# Schematic_car_like_pcb.net
KiCad netlist of a schematic drawn in Altium Designer
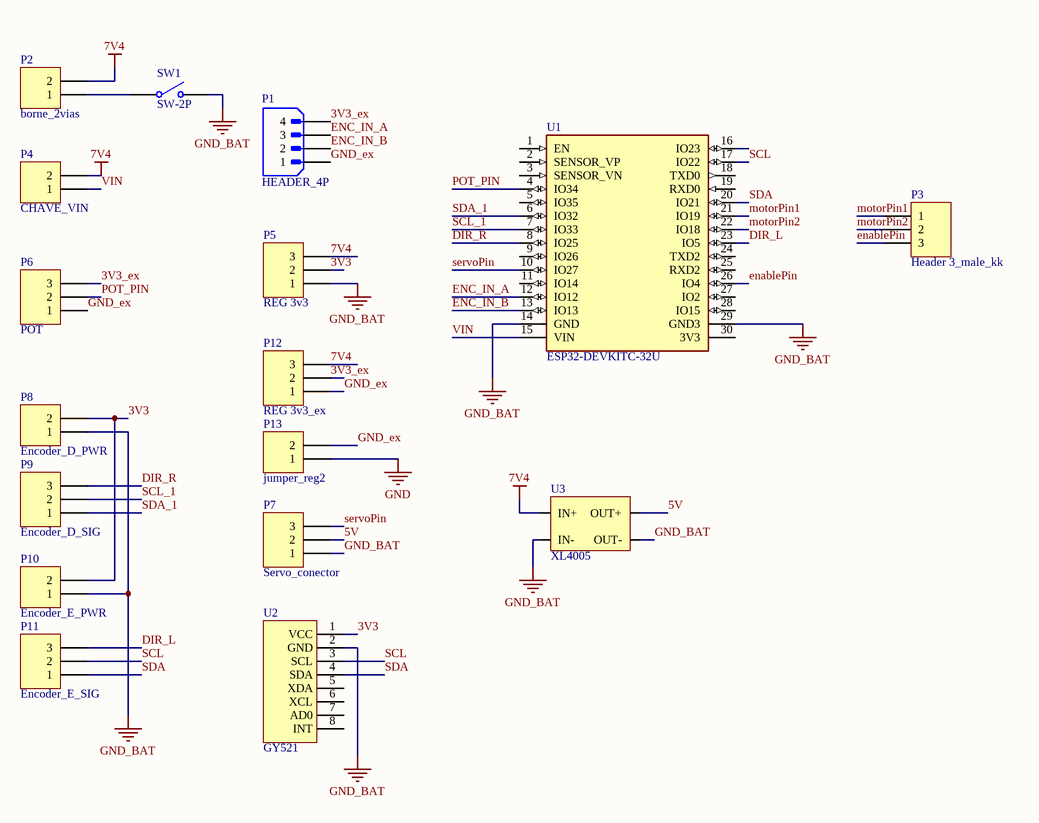
[diagram p0: Schematic_car_like_pcb.SchDoc]

(export (version "E")
  (design (tool "Eeschema 10.0.6"))
  (components
    (comp (ref "P1")
      (value "HEADER_4P")
      (footprint "HEADER_4PIN")
      (libsource (lib "CONNECTORS") (part "HEADER_4P"))
    )
    (comp (ref "P2")
      (value "borne_2vias")
      (footprint "BORNE_2VIAS")
      (libsource (lib "Connectors Library") (part "borne_2vias"))
    )
    (comp (ref "P3")
      (value "Header 3_male_kk")
      (footprint "HDR1X3_M - KK")
      (description "Header, 3-Pin")
      (fields (field (name "PUBLISHER") "Altium Limited"))
      (libsource (lib "") (part "Header 3_male_kk_1"))
    )
    (comp (ref "P4")
      (value "CHAVE_VIN")
      (footprint "HDR1X2_M - KK")
      (description "Header, 2-Pin")
      (fields (field (name "PUBLISHER") "Altium Limited"))
      (libsource (lib "Connectors Library") (part "Header 2_male_kk"))
    )
    (comp (ref "P5")
      (value "REG 3v3")
      (footprint "HDR1X3_F")
      (description "Header, 3-Pin")
      (fields (field (name "PUBLISHER") "Altium Limited"))
      (libsource (lib "Connectors Library") (part "Header 3_female"))
    )
    (comp (ref "P6")
      (value "POT")
      (footprint "HDR1X3_M - KK")
      (description "Header, 3-Pin")
      (fields (field (name "PUBLISHER") "Altium Limited"))
      (libsource (lib "Connectors Library") (part "Header 3_male_kk"))
    )
    (comp (ref "P7")
      (value "Servo_conector")
      (footprint "HDR1X3_M - KK")
      (description "Header, 3-Pin")
      (fields (field (name "PUBLISHER") "Altium Limited"))
      (libsource (lib "Connectors Library") (part "Header 3_male_kk"))
    )
    (comp (ref "P8")
      (value "Encoder_D_PWR")
      (footprint "HDR1X2_M - KK")
      (description "Header, 2-Pin")
      (fields (field (name "PUBLISHER") "Altium Limited"))
      (libsource (lib "Connectors Library") (part "Header 2_male_kk"))
    )
    (comp (ref "P9")
      (value "Encoder_D_SIG")
      (footprint "HDR1X3_M - KK")
      (description "Header, 3-Pin")
      (fields (field (name "PUBLISHER") "Altium Limited"))
      (libsource (lib "Connectors Library") (part "Header 3_male_kk"))
    )
    (comp (ref "P10")
      (value "Encoder_E_PWR")
      (footprint "HDR1X2_M - KK")
      (description "Header, 2-Pin")
      (fields (field (name "PUBLISHER") "Altium Limited"))
      (libsource (lib "Connectors Library") (part "Header 2_male_kk"))
    )
    (comp (ref "P11")
      (value "Encoder_E_SIG")
      (footprint "HDR1X3_M - KK")
      (description "Header, 3-Pin")
      (fields (field (name "PUBLISHER") "Altium Limited"))
      (libsource (lib "Connectors Library") (part "Header 3_male_kk"))
    )
    (comp (ref "P12")
      (value "REG 3v3_ex")
      (footprint "HDR1X3_F")
      (description "Header, 3-Pin")
      (fields (field (name "PUBLISHER") "Altium Limited"))
      (libsource (lib "Connectors Library") (part "Header 3_female"))
    )
    (comp (ref "P13")
      (value "jumper_reg2")
      (footprint "HDR1X2_M - KK")
      (description "Header, 2-Pin")
      (fields (field (name "PUBLISHER") "Altium Limited"))
      (libsource (lib "Connectors Library") (part "Header 2_male_kk"))
    )
    (comp (ref "SW1") (value "SW-2P") (footprint "SW-2") (libsource (lib "Devices") (part "SW-2P")))
    (comp (ref "U1")
      (value "ESP32-DEVKITC-32U")
      (footprint "ESP32S")
      (fields (field (name "MF") "Espressif Systems"))
      (libsource (lib "ESP32S") (part "ESP32-DEVKITC-32U"))
    )
    (comp (ref "U2") (value "GY521") (footprint "GY521") (libsource (lib "Devices") (part "GY521")))
    (comp (ref "U3") (value "XL4005") (footprint "XL4005") (libsource (lib "Devices") (part "XL4005")))
  )
  (nets
    (net (code "1") (name "/3V3") (class "Default")
      (node (ref "P10") (pin "2") (pinfunction "2_2") (pintype "passive"))
      (node (ref "P5") (pin "2") (pinfunction "2_2") (pintype "passive"))
      (node (ref "P8") (pin "2") (pinfunction "2_2") (pintype "passive"))
      (node (ref "U2") (pin "1") (pinfunction "VCC_1") (pintype "passive"))
    )
    (net (code "2") (name "/3V3_ex") (class "Default")
      (node (ref "P1") (pin "4") (pinfunction "4_4") (pintype "passive"))
      (node (ref "P12") (pin "2") (pinfunction "2_2") (pintype "passive"))
      (node (ref "P6") (pin "3") (pinfunction "3_3") (pintype "passive"))
    )
    (net (code "3") (name "/5V") (class "Default")
      (node (ref "P7") (pin "2") (pinfunction "2_2") (pintype "passive"))
      (node (ref "U3") (pin "4") (pinfunction "OUT+_4") (pintype "passive"))
    )
    (net (code "4") (name "/DIR_L") (class "Default")
      (node (ref "P11") (pin "3") (pinfunction "3_3") (pintype "passive"))
      (node (ref "U1") (pin "23") (pinfunction "IO5_23") (pintype "bidirectional"))
    )
    (net (code "5") (name "/DIR_R") (class "Default")
      (node (ref "P9") (pin "3") (pinfunction "3_3") (pintype "passive"))
      (node (ref "U1") (pin "8") (pinfunction "IO25_8") (pintype "bidirectional"))
    )
    (net (code "6") (name "/ENC_IN_A") (class "Default")
      (node (ref "P1") (pin "3") (pinfunction "3_3") (pintype "passive"))
      (node (ref "U1") (pin "12") (pinfunction "IO12_12") (pintype "bidirectional"))
    )
    (net (code "7") (name "/ENC_IN_B") (class "Default")
      (node (ref "P1") (pin "2") (pinfunction "2_2") (pintype "passive"))
      (node (ref "U1") (pin "13") (pinfunction "IO13_13") (pintype "bidirectional"))
    )
    (net (code "8") (name "/GND_ex") (class "Default")
      (node (ref "P1") (pin "1") (pinfunction "1_1") (pintype "passive"))
      (node (ref "P12") (pin "1") (pinfunction "1_1") (pintype "passive"))
      (node (ref "P13") (pin "2") (pinfunction "2_2") (pintype "passive"))
      (node (ref "P6") (pin "1") (pinfunction "1_1") (pintype "passive"))
    )
    (net (code "9") (name "/POT_PIN") (class "Default")
      (node (ref "P6") (pin "2") (pinfunction "2_2") (pintype "passive"))
      (node (ref "U1") (pin "4") (pinfunction "IO34_4") (pintype "bidirectional"))
    )
    (net (code "10") (name "/SCL") (class "Default")
      (node (ref "P11") (pin "2") (pinfunction "2_2") (pintype "passive"))
      (node (ref "U1") (pin "17") (pinfunction "IO22_17") (pintype "bidirectional"))
      (node (ref "U2") (pin "3") (pinfunction "SCL_3") (pintype "passive"))
    )
    (net (code "11") (name "/SCL_1") (class "Default")
      (node (ref "P9") (pin "2") (pinfunction "2_2") (pintype "passive"))
      (node (ref "U1") (pin "7") (pinfunction "IO33_7") (pintype "bidirectional"))
    )
    (net (code "12") (name "/SDA") (class "Default")
      (node (ref "P11") (pin "1") (pinfunction "1_1") (pintype "passive"))
      (node (ref "U1") (pin "20") (pinfunction "IO21_20") (pintype "bidirectional"))
      (node (ref "U2") (pin "4") (pinfunction "SDA_4") (pintype "passive"))
    )
    (net (code "13") (name "/SDA_1") (class "Default")
      (node (ref "P9") (pin "1") (pinfunction "1_1") (pintype "passive"))
      (node (ref "U1") (pin "6") (pinfunction "IO32_6") (pintype "bidirectional"))
    )
    (net (code "14") (name "/VIN") (class "Default")
      (node (ref "P4") (pin "1") (pinfunction "1_1") (pintype "passive"))
      (node (ref "U1") (pin "15") (pinfunction "VIN_15") (pintype "power_in"))
    )
    (net (code "15") (name "/enablePin") (class "Default")
      (node (ref "P3") (pin "3") (pinfunction "3_3") (pintype "passive"))
      (node (ref "U1") (pin "26") (pinfunction "IO4_26") (pintype "bidirectional"))
    )
    (net (code "16") (name "/motorPin1") (class "Default")
      (node (ref "P3") (pin "1") (pinfunction "1_1") (pintype "passive"))
      (node (ref "U1") (pin "21") (pinfunction "IO19_21") (pintype "bidirectional"))
    )
    (net (code "17") (name "/motorPin2") (class "Default")
      (node (ref "P3") (pin "2") (pinfunction "2_2") (pintype "passive"))
      (node (ref "U1") (pin "22") (pinfunction "IO18_22") (pintype "bidirectional"))
    )
    (net (code "18") (name "/servoPin") (class "Default")
      (node (ref "P7") (pin "3") (pinfunction "3_3") (pintype "passive"))
      (node (ref "U1") (pin "10") (pinfunction "IO27_10") (pintype "bidirectional"))
    )
    (net (code "19") (name "7V4") (class "Default")
      (node (ref "P12") (pin "3") (pinfunction "3_3") (pintype "passive"))
      (node (ref "P2") (pin "2") (pinfunction "2_2") (pintype "passive"))
      (node (ref "P4") (pin "2") (pinfunction "2_2") (pintype "passive"))
      (node (ref "P5") (pin "3") (pinfunction "3_3") (pintype "passive"))
      (node (ref "U3") (pin "2") (pinfunction "IN+_2") (pintype "passive"))
    )
    (net (code "20") (name "GND") (class "Default")
      (node (ref "P13") (pin "1") (pinfunction "1_1") (pintype "passive"))
    )
    (net (code "21") (name "GND_BAT") (class "Default")
      (node (ref "P10") (pin "1") (pinfunction "1_1") (pintype "passive"))
      (node (ref "P5") (pin "1") (pinfunction "1_1") (pintype "passive"))
      (node (ref "P7") (pin "1") (pinfunction "1_1") (pintype "passive"))
      (node (ref "P8") (pin "1") (pinfunction "1_1") (pintype "passive"))
      (node (ref "SW1") (pin "2") (pinfunction "NO_2") (pintype "passive"))
      (node (ref "U1") (pin "14") (pinfunction "GND_14") (pintype "power_in"))
      (node (ref "U1") (pin "29") (pinfunction "GND3_29") (pintype "power_in"))
      (node (ref "U2") (pin "2") (pinfunction "GND_2") (pintype "passive"))
      (node (ref "U3") (pin "1") (pinfunction "IN-_1") (pintype "passive"))
      (node (ref "U3") (pin "3") (pinfunction "OUT-_3") (pintype "passive"))
    )
    (net (code "22") (name "Net-(SW1-COMMON)") (class "Default")
      (node (ref "P2") (pin "1") (pinfunction "1_1") (pintype "passive"))
      (node (ref "SW1") (pin "1") (pinfunction "COMMON_1") (pintype "passive"))
    )
    (net (code "23") (name "unconnected-(U1-3V3-Pad30)") (class "Default")
      (node (ref "U1") (pin "30") (pinfunction "3V3_30") (pintype "power_in"))
    )
    (net (code "24") (name "unconnected-(U1-EN-Pad1)") (class "Default")
      (node (ref "U1") (pin "1") (pinfunction "EN_1") (pintype "input"))
    )
    (net (code "25") (name "unconnected-(U1-IO2-Pad27)") (class "Default")
      (node (ref "U1") (pin "27") (pinfunction "IO2_27") (pintype "bidirectional"))
    )
    (net (code "26") (name "unconnected-(U1-IO14-Pad11)") (class "Default")
      (node (ref "U1") (pin "11") (pinfunction "IO14_11") (pintype "bidirectional"))
    )
    (net (code "27") (name "unconnected-(U1-IO15-Pad28)") (class "Default")
      (node (ref "U1") (pin "28") (pinfunction "IO15_28") (pintype "bidirectional"))
    )
    (net (code "28") (name "unconnected-(U1-IO23-Pad16)") (class "Default")
      (node (ref "U1") (pin "16") (pinfunction "IO23_16") (pintype "bidirectional"))
    )
    (net (code "29") (name "unconnected-(U1-IO26-Pad9)") (class "Default")
      (node (ref "U1") (pin "9") (pinfunction "IO26_9") (pintype "bidirectional"))
    )
    (net (code "30") (name "unconnected-(U1-IO35-Pad5)") (class "Default")
      (node (ref "U1") (pin "5") (pinfunction "IO35_5") (pintype "bidirectional"))
    )
    (net (code "31") (name "unconnected-(U1-RXD0-Pad19)") (class "Default")
      (node (ref "U1") (pin "19") (pinfunction "RXD0_19") (pintype "input"))
    )
    (net (code "32") (name "unconnected-(U1-RXD2-Pad25)") (class "Default")
      (node (ref "U1") (pin "25") (pinfunction "RXD2_25") (pintype "bidirectional"))
    )
    (net (code "33") (name "unconnected-(U1-SENSOR_VN-Pad3)") (class "Default")
      (node (ref "U1") (pin "3") (pinfunction "SENSOR_VN_3") (pintype "input"))
    )
    (net (code "34") (name "unconnected-(U1-SENSOR_VP-Pad2)") (class "Default")
      (node (ref "U1") (pin "2") (pinfunction "SENSOR_VP_2") (pintype "input"))
    )
    (net (code "35") (name "unconnected-(U1-TXD0-Pad18)") (class "Default")
      (node (ref "U1") (pin "18") (pinfunction "TXD0_18") (pintype "output"))
    )
    (net (code "36") (name "unconnected-(U1-TXD2-Pad24)") (class "Default")
      (node (ref "U1") (pin "24") (pinfunction "TXD2_24") (pintype "bidirectional"))
    )
    (net (code "37") (name "unconnected-(U2-AD0-Pad7)") (class "Default")
      (node (ref "U2") (pin "7") (pinfunction "AD0_7") (pintype "passive"))
    )
    (net (code "38") (name "unconnected-(U2-INT-Pad8)") (class "Default")
      (node (ref "U2") (pin "8") (pinfunction "INT_8") (pintype "passive"))
    )
    (net (code "39") (name "unconnected-(U2-XCL-Pad6)") (class "Default")
      (node (ref "U2") (pin "6") (pinfunction "XCL_6") (pintype "passive"))
    )
    (net (code "40") (name "unconnected-(U2-XDA-Pad5)") (class "Default")
      (node (ref "U2") (pin "5") (pinfunction "XDA_5") (pintype "passive"))
    )
  )
)
